# STM32L4xx-v1_2_0.net
KiCad netlist of a schematic drawn in EAGLE
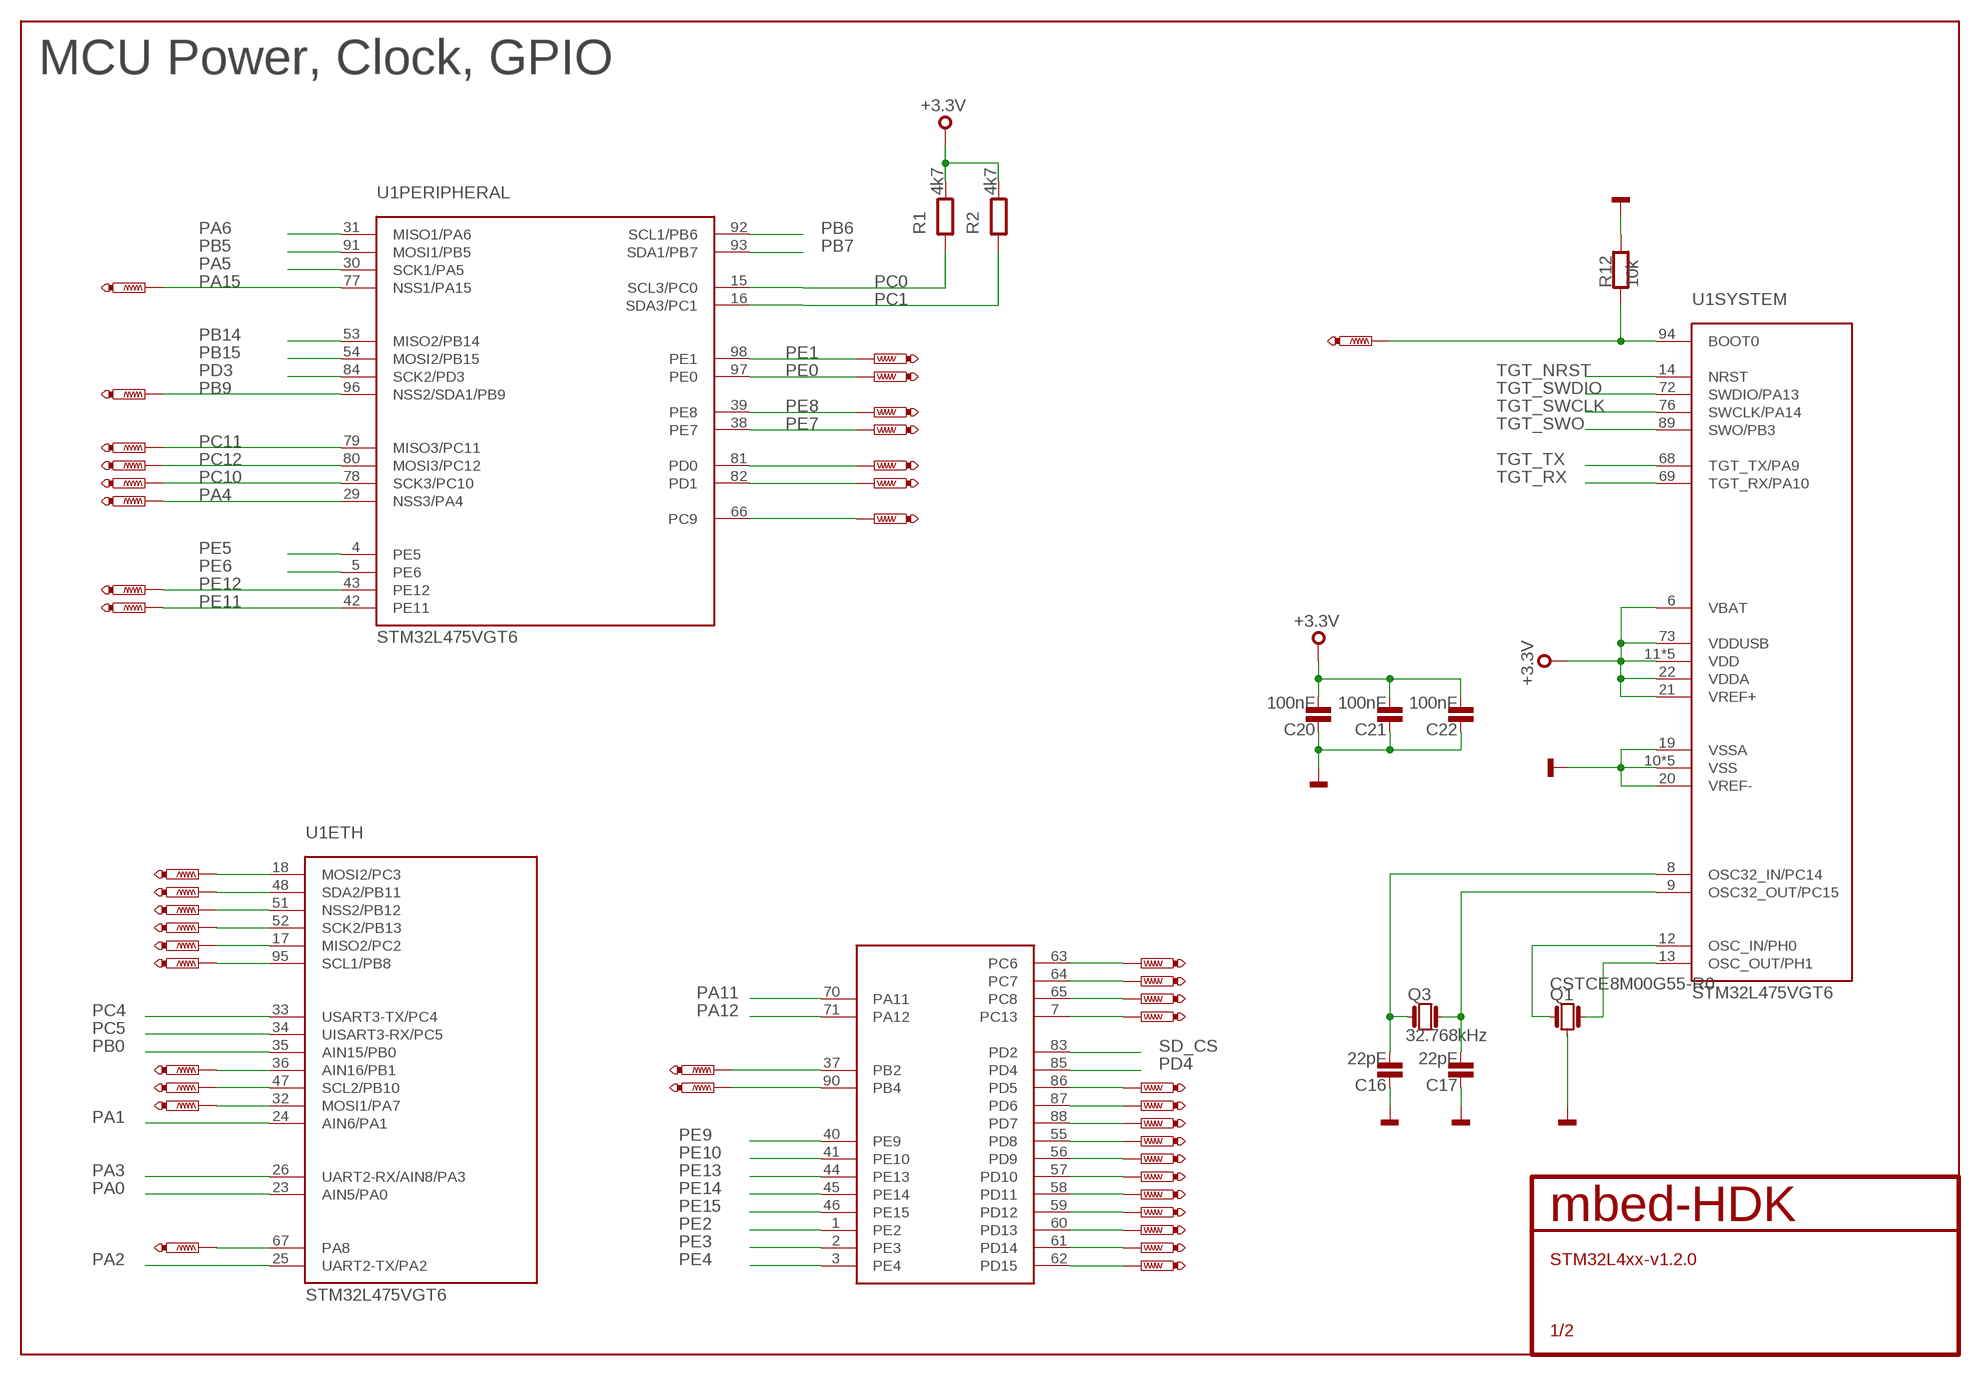
[diagram p0: schematic, sheet 1]
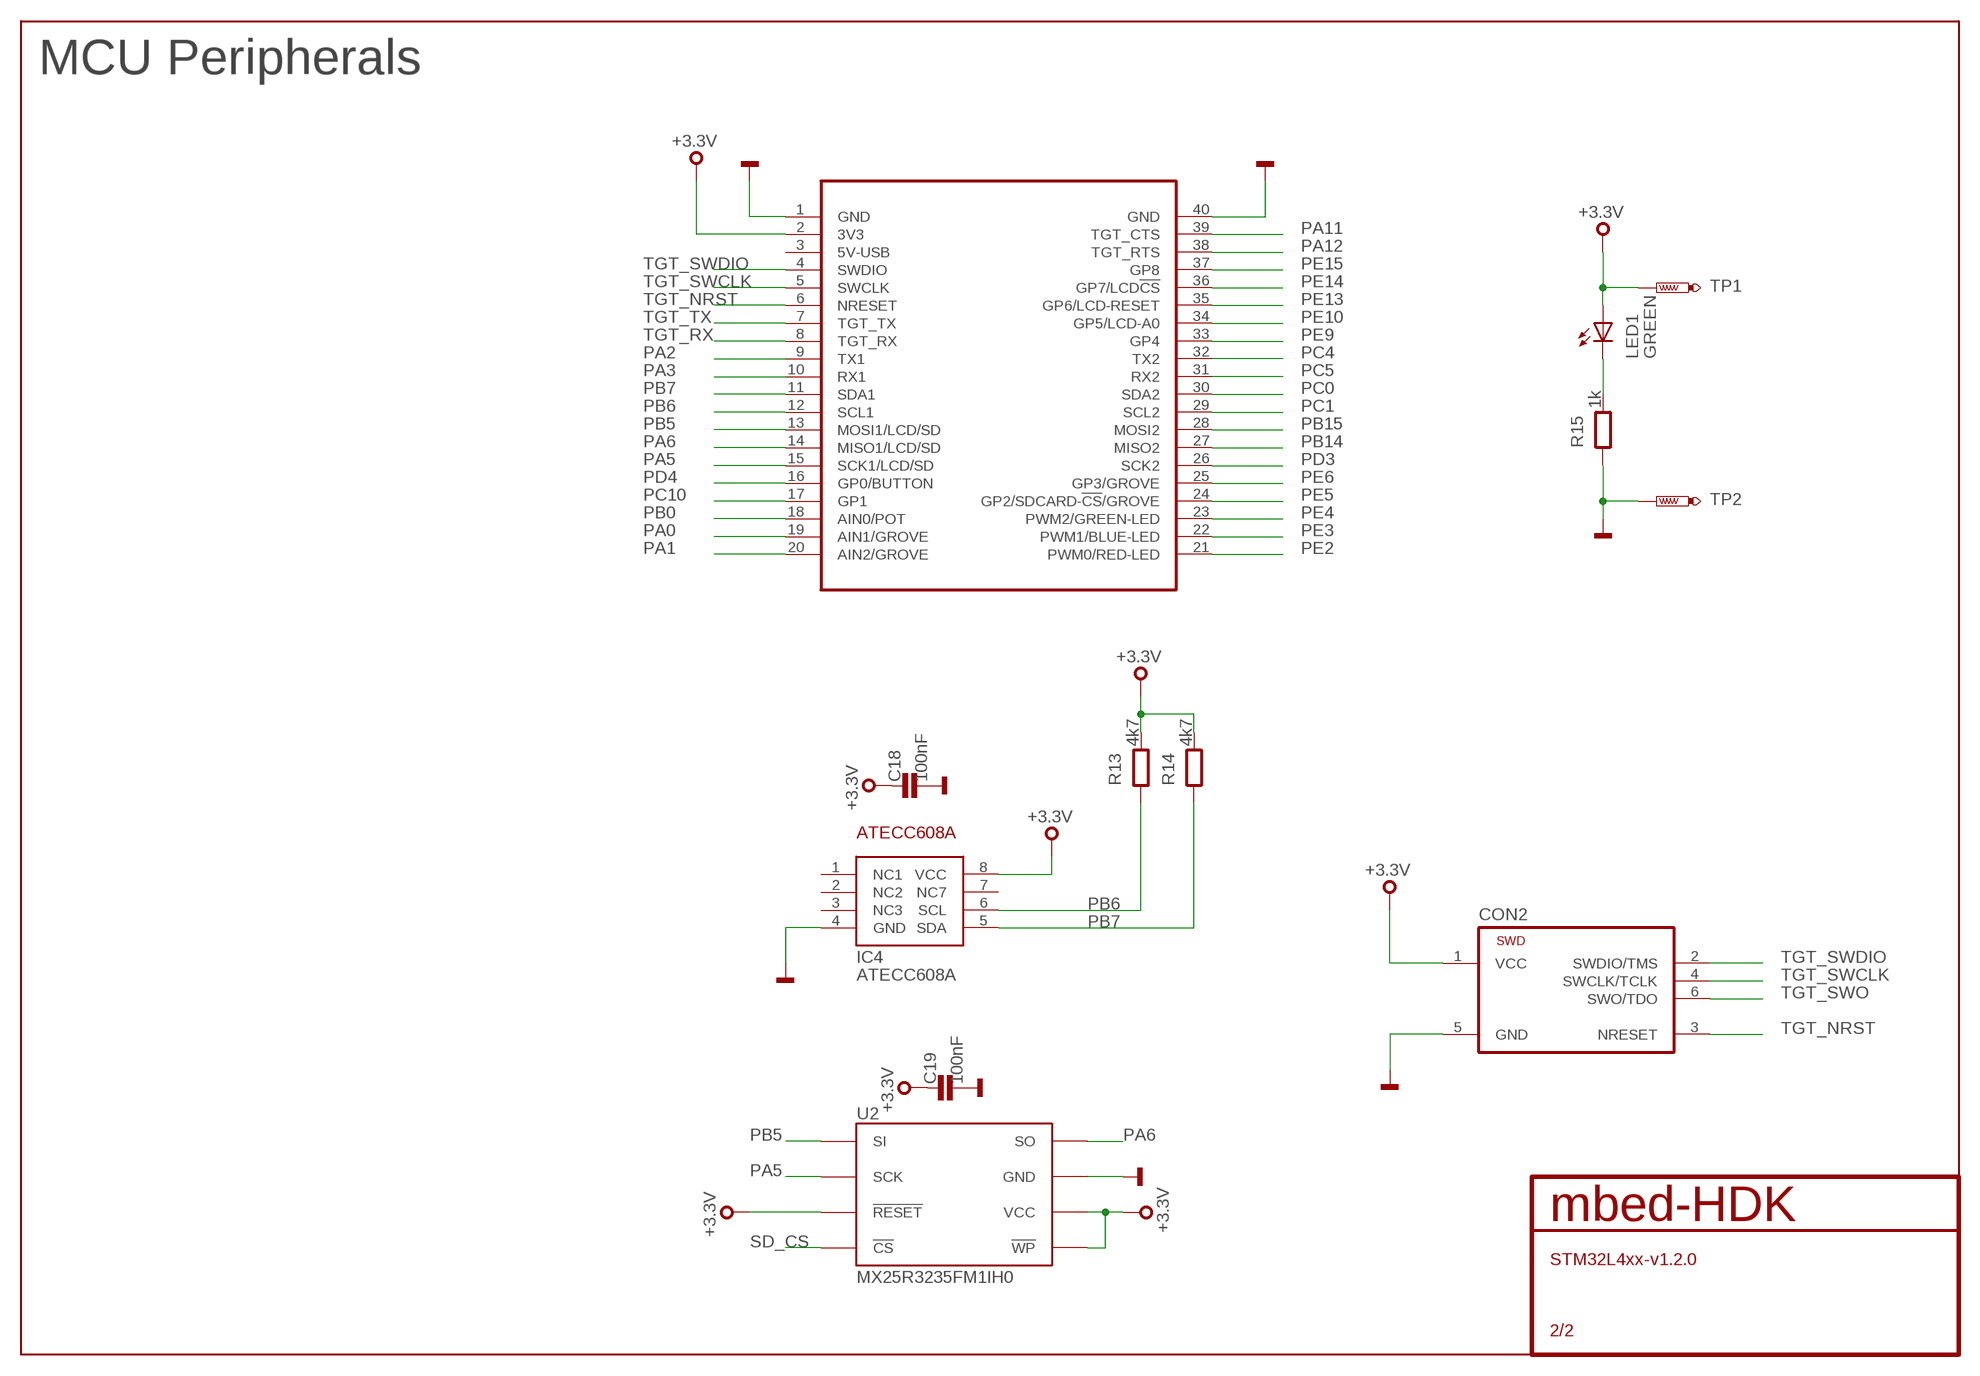
[diagram p1: schematic, sheet 2]

(export (version "E")
  (design (tool "Eeschema 10.0.6"))
  (components
    (comp (ref "C18")
      (value "100nF")
      (footprint "eagle-import:0402")
      (libsource (lib "eagle-import") (part "C0402"))
    )
    (comp (ref "C19")
      (value "100nF")
      (footprint "eagle-import:0402")
      (libsource (lib "eagle-import") (part "C0402"))
    )
    (comp (ref "CON2")
      (value "TC2030-CTX-NL")
      (footprint "eagle-import:TC2030-CTX-NL")
      (libsource (lib "eagle-import") (part "TC2030-CTX-NL"))
    )
    (comp (ref "IC4")
      (value "ATECC608A")
      (footprint "eagle-import:SO8")
      (libsource (lib "eagle-import") (part "ATECC608A"))
    )
    (comp (ref "LED1")
      (value "GREEN")
      (footprint "eagle-import:CHIPLED_0603")
      (fields (field (name "MF") "Wurth Electronics Inc"))
      (libsource (lib "eagle-import") (part "SMD_LED0603"))
    )
    (comp (ref "MOD1")
      (value "MODULE_DAUGHTER")
      (footprint "eagle-import:MODULE_DAUGHTER")
      (libsource (lib "eagle-import") (part "MODULE_DAUGHTER"))
    )
    (comp (ref "R13")
      (value "4k7")
      (footprint "eagle-import:0402")
      (libsource (lib "eagle-import") (part "R0402"))
    )
    (comp (ref "R14")
      (value "4k7")
      (footprint "eagle-import:0402")
      (libsource (lib "eagle-import") (part "R0402"))
    )
    (comp (ref "R15")
      (value "1k")
      (footprint "eagle-import:0603")
      (libsource (lib "eagle-import") (part "R0603"))
    )
    (comp (ref "TP1")
      (value "TEST_POINT-50R-PTH")
      (footprint "eagle-import:TP50-PTH")
      (libsource (lib "eagle-import") (part "TEST_POINT-50R-PTH"))
    )
    (comp (ref "TP2")
      (value "TEST_POINT-50R-PTH")
      (footprint "eagle-import:TP50-PTH")
      (libsource (lib "eagle-import") (part "TEST_POINT-50R-PTH"))
    )
    (comp (ref "U2")
      (value "MX25R3235FM1IH0")
      (footprint "eagle-import:SO8")
      (fields (field (name "MF") "Macronix"))
      (libsource (lib "eagle-import") (part "MX25R3235FM1IH0"))
    )
    (comp (ref "C16")
      (value "22pF")
      (footprint "eagle-import:0603")
      (libsource (lib "eagle-import") (part "C0603"))
    )
    (comp (ref "C17")
      (value "22pF")
      (footprint "eagle-import:0603")
      (libsource (lib "eagle-import") (part "C0603"))
    )
    (comp (ref "C20")
      (value "100nF")
      (footprint "eagle-import:0402")
      (libsource (lib "eagle-import") (part "C0402"))
    )
    (comp (ref "C21")
      (value "100nF")
      (footprint "eagle-import:0402")
      (libsource (lib "eagle-import") (part "C0402"))
    )
    (comp (ref "C22")
      (value "100nF")
      (footprint "eagle-import:0402")
      (libsource (lib "eagle-import") (part "C0402"))
    )
    (comp (ref "Q1")
      (value "CSTCE8M00G55-R0")
      (footprint "eagle-import:CSTCE8M00G55-R0")
      (fields (field (name "MF") "Murata"))
      (libsource (lib "eagle-import") (part "CSTCE8M00G55-R0"))
    )
    (comp (ref "Q3")
      (value "32.768kHz")
      (footprint "eagle-import:FC135")
      (libsource (lib "eagle-import") (part "GENERIC-CRYSTAL_FC135"))
    )
    (comp (ref "R1")
      (value "4k7")
      (footprint "eagle-import:0402")
      (libsource (lib "eagle-import") (part "R0402"))
    )
    (comp (ref "R2")
      (value "4k7")
      (footprint "eagle-import:0402")
      (libsource (lib "eagle-import") (part "R0402"))
    )
    (comp (ref "R12")
      (value "10k")
      (footprint "eagle-import:0402")
      (libsource (lib "eagle-import") (part "R0402"))
    )
    (comp (ref "TP3")
      (value "PTR1TP06R")
      (footprint "eagle-import:TP06R")
      (libsource (lib "eagle-import") (part "PTR1TP06R"))
    )
    (comp (ref "TP4")
      (value "PTR1TP06R")
      (footprint "eagle-import:TP06R")
      (libsource (lib "eagle-import") (part "PTR1TP06R"))
    )
    (comp (ref "TP5")
      (value "PTR1TP06R")
      (footprint "eagle-import:TP06R")
      (libsource (lib "eagle-import") (part "PTR1TP06R"))
    )
    (comp (ref "TP6")
      (value "PTR1TP06R")
      (footprint "eagle-import:TP06R")
      (libsource (lib "eagle-import") (part "PTR1TP06R"))
    )
    (comp (ref "TP7")
      (value "PTR1TP06R")
      (footprint "eagle-import:TP06R")
      (libsource (lib "eagle-import") (part "PTR1TP06R"))
    )
    (comp (ref "TP8")
      (value "PTR1TP06R")
      (footprint "eagle-import:TP06R")
      (libsource (lib "eagle-import") (part "PTR1TP06R"))
    )
    (comp (ref "TP9")
      (value "PTR1TP06R")
      (footprint "eagle-import:TP06R")
      (libsource (lib "eagle-import") (part "PTR1TP06R"))
    )
    (comp (ref "TP10")
      (value "PTR1TP06R")
      (footprint "eagle-import:TP06R")
      (libsource (lib "eagle-import") (part "PTR1TP06R"))
    )
    (comp (ref "TP11")
      (value "PTR1TP06R")
      (footprint "eagle-import:TP06R")
      (libsource (lib "eagle-import") (part "PTR1TP06R"))
    )
    (comp (ref "TP12")
      (value "PTR1TP06R")
      (footprint "eagle-import:TP06R")
      (libsource (lib "eagle-import") (part "PTR1TP06R"))
    )
    (comp (ref "TP13")
      (value "PTR1TP06R")
      (footprint "eagle-import:TP06R")
      (libsource (lib "eagle-import") (part "PTR1TP06R"))
    )
    (comp (ref "TP14")
      (value "PTR1TP06R")
      (footprint "eagle-import:TP06R")
      (libsource (lib "eagle-import") (part "PTR1TP06R"))
    )
    (comp (ref "TP15")
      (value "PTR1TP06R")
      (footprint "eagle-import:TP06R")
      (libsource (lib "eagle-import") (part "PTR1TP06R"))
    )
    (comp (ref "TP16")
      (value "PTR1TP06R")
      (footprint "eagle-import:TP06R")
      (libsource (lib "eagle-import") (part "PTR1TP06R"))
    )
    (comp (ref "TP17")
      (value "PTR1TP06R")
      (footprint "eagle-import:TP06R")
      (libsource (lib "eagle-import") (part "PTR1TP06R"))
    )
    (comp (ref "TP18")
      (value "PTR1TP06R")
      (footprint "eagle-import:TP06R")
      (libsource (lib "eagle-import") (part "PTR1TP06R"))
    )
    (comp (ref "TP19")
      (value "PTR1TP06R")
      (footprint "eagle-import:TP06R")
      (libsource (lib "eagle-import") (part "PTR1TP06R"))
    )
    (comp (ref "TP20")
      (value "PTR1TP06R")
      (footprint "eagle-import:TP06R")
      (libsource (lib "eagle-import") (part "PTR1TP06R"))
    )
    (comp (ref "TP21")
      (value "PTR1TP06R")
      (footprint "eagle-import:TP06R")
      (libsource (lib "eagle-import") (part "PTR1TP06R"))
    )
    (comp (ref "TP22")
      (value "PTR1TP06R")
      (footprint "eagle-import:TP06R")
      (libsource (lib "eagle-import") (part "PTR1TP06R"))
    )
    (comp (ref "TP23")
      (value "PTR1TP06R")
      (footprint "eagle-import:TP06R")
      (libsource (lib "eagle-import") (part "PTR1TP06R"))
    )
    (comp (ref "TP24")
      (value "PTR1TP06R")
      (footprint "eagle-import:TP06R")
      (libsource (lib "eagle-import") (part "PTR1TP06R"))
    )
    (comp (ref "TP25")
      (value "PTR1TP06R")
      (footprint "eagle-import:TP06R")
      (libsource (lib "eagle-import") (part "PTR1TP06R"))
    )
    (comp (ref "TP26")
      (value "PTR1TP06R")
      (footprint "eagle-import:TP06R")
      (libsource (lib "eagle-import") (part "PTR1TP06R"))
    )
    (comp (ref "TP27")
      (value "PTR1TP06R")
      (footprint "eagle-import:TP06R")
      (libsource (lib "eagle-import") (part "PTR1TP06R"))
    )
    (comp (ref "TP28")
      (value "PTR1TP06R")
      (footprint "eagle-import:TP06R")
      (libsource (lib "eagle-import") (part "PTR1TP06R"))
    )
    (comp (ref "TP29")
      (value "PTR1TP06R")
      (footprint "eagle-import:TP06R")
      (libsource (lib "eagle-import") (part "PTR1TP06R"))
    )
    (comp (ref "TP30")
      (value "PTR1TP06R")
      (footprint "eagle-import:TP06R")
      (libsource (lib "eagle-import") (part "PTR1TP06R"))
    )
    (comp (ref "TP31")
      (value "PTR1TP06R")
      (footprint "eagle-import:TP06R")
      (libsource (lib "eagle-import") (part "PTR1TP06R"))
    )
    (comp (ref "TP32")
      (value "PTR1TP06R")
      (footprint "eagle-import:TP06R")
      (libsource (lib "eagle-import") (part "PTR1TP06R"))
    )
    (comp (ref "TP33")
      (value "PTR1TP06R")
      (footprint "eagle-import:TP06R")
      (libsource (lib "eagle-import") (part "PTR1TP06R"))
    )
    (comp (ref "TP34")
      (value "PTR1TP06R")
      (footprint "eagle-import:TP06R")
      (libsource (lib "eagle-import") (part "PTR1TP06R"))
    )
    (comp (ref "TP35")
      (value "PTR1TP06R")
      (footprint "eagle-import:TP06R")
      (libsource (lib "eagle-import") (part "PTR1TP06R"))
    )
    (comp (ref "TP36")
      (value "PTR1TP06R")
      (footprint "eagle-import:TP06R")
      (libsource (lib "eagle-import") (part "PTR1TP06R"))
    )
    (comp (ref "TP37")
      (value "PTR1TP06R")
      (footprint "eagle-import:TP06R")
      (libsource (lib "eagle-import") (part "PTR1TP06R"))
    )
    (comp (ref "TP38")
      (value "PTR1TP06R")
      (footprint "eagle-import:TP06R")
      (libsource (lib "eagle-import") (part "PTR1TP06R"))
    )
    (comp (ref "TP39")
      (value "PTR1TP06R")
      (footprint "eagle-import:TP06R")
      (libsource (lib "eagle-import") (part "PTR1TP06R"))
    )
    (comp (ref "TP40")
      (value "PTR1TP06R")
      (footprint "eagle-import:TP06R")
      (libsource (lib "eagle-import") (part "PTR1TP06R"))
    )
    (comp (ref "TP41")
      (value "PTR1TP06R")
      (footprint "eagle-import:TP06R")
      (libsource (lib "eagle-import") (part "PTR1TP06R"))
    )
    (comp (ref "TP42")
      (value "PTR1TP06R")
      (footprint "eagle-import:TP06R")
      (libsource (lib "eagle-import") (part "PTR1TP06R"))
    )
    (comp (ref "TP43")
      (value "PTR1TP06R")
      (footprint "eagle-import:TP06R")
      (libsource (lib "eagle-import") (part "PTR1TP06R"))
    )
    (comp (ref "TP44")
      (value "PTR1TP06R")
      (footprint "eagle-import:TP06R")
      (libsource (lib "eagle-import") (part "PTR1TP06R"))
    )
    (comp (ref "TP45")
      (value "PTR1TP06R")
      (footprint "eagle-import:TP06R")
      (libsource (lib "eagle-import") (part "PTR1TP06R"))
    )
    (comp (ref "U1")
      (value "STM32L475VGT6")
      (footprint "eagle-import:QFP50P1600X1600X160-100N")
      (libsource (lib "eagle-import") (part "STM32L475VGT6"))
    )
  )
  (nets
    (net (code "1") (name "+3.3V") (class "Default")
      (node (ref "C18") (pin "1") (pinfunction "P$1_1") (pintype "passive"))
      (node (ref "C19") (pin "1") (pinfunction "P$1_1") (pintype "passive"))
      (node (ref "C20") (pin "2") (pinfunction "P$2_2") (pintype "passive"))
      (node (ref "C21") (pin "2") (pinfunction "P$2_2") (pintype "passive"))
      (node (ref "C22") (pin "2") (pinfunction "P$2_2") (pintype "passive"))
      (node (ref "CON2") (pin "1") (pinfunction "VCC_1") (pintype "passive"))
      (node (ref "IC4") (pin "8") (pinfunction "VCC_8") (pintype "bidirectional"))
      (node (ref "LED1") (pin "A") (pinfunction "A_A") (pintype "passive"))
      (node (ref "MOD1") (pin "2") (pinfunction "3V3_2") (pintype "bidirectional"))
      (node (ref "R1") (pin "2") (pinfunction "P$2_2") (pintype "passive"))
      (node (ref "R13") (pin "2") (pinfunction "P$2_2") (pintype "passive"))
      (node (ref "R14") (pin "2") (pinfunction "P$2_2") (pintype "passive"))
      (node (ref "R2") (pin "2") (pinfunction "P$2_2") (pintype "passive"))
      (node (ref "TP1") (pin "TP") (pinfunction "TP_TP") (pintype "input"))
      (node (ref "U1") (pin "100") (pinfunction "VDD_100") (pintype "power_in"))
      (node (ref "U1") (pin "11") (pinfunction "VDD_11") (pintype "power_in"))
      (node (ref "U1") (pin "21") (pinfunction "VREF+_21") (pintype "power_in"))
      (node (ref "U1") (pin "22") (pinfunction "VDDA_22") (pintype "power_in"))
      (node (ref "U1") (pin "28") (pinfunction "VDD_28") (pintype "power_in"))
      (node (ref "U1") (pin "50") (pinfunction "VDD_50") (pintype "power_in"))
      (node (ref "U1") (pin "6") (pinfunction "VBAT_6") (pintype "power_in"))
      (node (ref "U1") (pin "73") (pinfunction "VDDUSB_73") (pintype "power_in"))
      (node (ref "U1") (pin "75") (pinfunction "VDD_75") (pintype "power_in"))
      (node (ref "U2") (pin "3") (pinfunction "~{WP}_3") (pintype "bidirectional"))
      (node (ref "U2") (pin "7") (pinfunction "~{RESET}_7") (pintype "bidirectional"))
      (node (ref "U2") (pin "8") (pinfunction "VCC_8") (pintype "bidirectional"))
    )
    (net (code "2") (name "GND") (class "Default")
      (node (ref "C16") (pin "1") (pinfunction "P$1_1") (pintype "passive"))
      (node (ref "C17") (pin "1") (pinfunction "P$1_1") (pintype "passive"))
      (node (ref "C18") (pin "2") (pinfunction "P$2_2") (pintype "passive"))
      (node (ref "C19") (pin "2") (pinfunction "P$2_2") (pintype "passive"))
      (node (ref "C20") (pin "1") (pinfunction "P$1_1") (pintype "passive"))
      (node (ref "C21") (pin "1") (pinfunction "P$1_1") (pintype "passive"))
      (node (ref "C22") (pin "1") (pinfunction "P$1_1") (pintype "passive"))
      (node (ref "CON2") (pin "5") (pinfunction "GND_5") (pintype "passive"))
      (node (ref "IC4") (pin "4") (pinfunction "GND_4") (pintype "bidirectional"))
      (node (ref "MOD1") (pin "1") (pinfunction "GND_1") (pintype "bidirectional"))
      (node (ref "MOD1") (pin "40") (pinfunction "GND_40") (pintype "bidirectional"))
      (node (ref "Q1") (pin "2") (pinfunction "2_2") (pintype "passive"))
      (node (ref "R12") (pin "2") (pinfunction "P$2_2") (pintype "passive"))
      (node (ref "R15") (pin "1") (pinfunction "P$1_1") (pintype "passive"))
      (node (ref "TP2") (pin "TP") (pinfunction "TP_TP") (pintype "input"))
      (node (ref "U1") (pin "10") (pinfunction "VSS_10") (pintype "power_in"))
      (node (ref "U1") (pin "19") (pinfunction "VSSA_19") (pintype "power_in"))
      (node (ref "U1") (pin "20") (pinfunction "VREF-_20") (pintype "power_in"))
      (node (ref "U1") (pin "27") (pinfunction "VSS_27") (pintype "power_in"))
      (node (ref "U1") (pin "49") (pinfunction "VSS_49") (pintype "power_in"))
      (node (ref "U1") (pin "74") (pinfunction "VSS_74") (pintype "power_in"))
      (node (ref "U1") (pin "99") (pinfunction "VSS_99") (pintype "power_in"))
      (node (ref "U2") (pin "4") (pinfunction "GND_4") (pintype "bidirectional"))
    )
    (net (code "3") (name "Net-(C16-P$2)") (class "Default")
      (node (ref "C16") (pin "2") (pinfunction "P$2_2") (pintype "passive"))
      (node (ref "Q3") (pin "X1") (pinfunction "1_X1") (pintype "passive"))
      (node (ref "U1") (pin "8") (pinfunction "OSC32_IN/PC14_8") (pintype "bidirectional"))
    )
    (net (code "4") (name "Net-(C17-P$2)") (class "Default")
      (node (ref "C17") (pin "2") (pinfunction "P$2_2") (pintype "passive"))
      (node (ref "Q3") (pin "X2") (pinfunction "2_X2") (pintype "passive"))
      (node (ref "U1") (pin "9") (pinfunction "OSC32_OUT/PC15_9") (pintype "bidirectional"))
    )
    (net (code "5") (name "Net-(R12-P$1)") (class "Default")
      (node (ref "R12") (pin "1") (pinfunction "P$1_1") (pintype "passive"))
      (node (ref "TP6") (pin "TP") (pinfunction "TP_TP") (pintype "input"))
      (node (ref "U1") (pin "94") (pinfunction "BOOT0_94") (pintype "input"))
    )
    (net (code "6") (name "Net-(R15-P$2)") (class "Default")
      (node (ref "LED1") (pin "C") (pinfunction "C_C") (pintype "passive"))
      (node (ref "R15") (pin "2") (pinfunction "P$2_2") (pintype "passive"))
    )
    (net (code "7") (name "Net-(U1A-AIN16{slash}PB1)") (class "Default")
      (node (ref "TP34") (pin "TP") (pinfunction "TP_TP") (pintype "input"))
      (node (ref "U1") (pin "36") (pinfunction "AIN16/PB1_36") (pintype "bidirectional"))
    )
    (net (code "8") (name "Net-(U1A-MISO2{slash}PC2)") (class "Default")
      (node (ref "TP31") (pin "TP") (pinfunction "TP_TP") (pintype "input"))
      (node (ref "U1") (pin "17") (pinfunction "MISO2/PC2_17") (pintype "bidirectional"))
    )
    (net (code "9") (name "Net-(U1A-MOSI1{slash}PA7)") (class "Default")
      (node (ref "TP35") (pin "TP") (pinfunction "TP_TP") (pintype "input"))
      (node (ref "U1") (pin "32") (pinfunction "MOSI1/PA7_32") (pintype "bidirectional"))
    )
    (net (code "10") (name "Net-(U1A-MOSI2{slash}PC3)") (class "Default")
      (node (ref "TP27") (pin "TP") (pinfunction "TP_TP") (pintype "input"))
      (node (ref "U1") (pin "18") (pinfunction "MOSI2/PC3_18") (pintype "bidirectional"))
    )
    (net (code "11") (name "Net-(U1A-NSS2{slash}PB12)") (class "Default")
      (node (ref "TP29") (pin "TP") (pinfunction "TP_TP") (pintype "input"))
      (node (ref "U1") (pin "51") (pinfunction "NSS2/PB12_51") (pintype "bidirectional"))
    )
    (net (code "12") (name "Net-(U1A-PA8)") (class "Default")
      (node (ref "TP33") (pin "TP") (pinfunction "TP_TP") (pintype "input"))
      (node (ref "U1") (pin "67") (pinfunction "PA8_67") (pintype "bidirectional"))
    )
    (net (code "13") (name "Net-(U1A-SCK2{slash}PB13)") (class "Default")
      (node (ref "TP30") (pin "TP") (pinfunction "TP_TP") (pintype "input"))
      (node (ref "U1") (pin "52") (pinfunction "SCK2/PB13_52") (pintype "bidirectional"))
    )
    (net (code "14") (name "Net-(U1A-SCL1{slash}PB8)") (class "Default")
      (node (ref "TP32") (pin "TP") (pinfunction "TP_TP") (pintype "input"))
      (node (ref "U1") (pin "95") (pinfunction "SCL1/PB8_95") (pintype "bidirectional"))
    )
    (net (code "15") (name "Net-(U1A-SCL2{slash}PB10)") (class "Default")
      (node (ref "TP36") (pin "TP") (pinfunction "TP_TP") (pintype "input"))
      (node (ref "U1") (pin "47") (pinfunction "SCL2/PB10_47") (pintype "bidirectional"))
    )
    (net (code "16") (name "Net-(U1A-SDA2{slash}PB11)") (class "Default")
      (node (ref "TP28") (pin "TP") (pinfunction "TP_TP") (pintype "input"))
      (node (ref "U1") (pin "48") (pinfunction "SDA2/PB11_48") (pintype "bidirectional"))
    )
    (net (code "17") (name "Net-(U1B-PB2)") (class "Default")
      (node (ref "TP26") (pin "TP") (pinfunction "TP_TP") (pintype "input"))
      (node (ref "U1") (pin "37") (pinfunction "PB2_37") (pintype "bidirectional"))
    )
    (net (code "18") (name "Net-(U1B-PB4)") (class "Default")
      (node (ref "TP11") (pin "TP") (pinfunction "TP_TP") (pintype "input"))
      (node (ref "U1") (pin "90") (pinfunction "PB4_90") (pintype "bidirectional"))
    )
    (net (code "19") (name "Net-(U1B-PC6)") (class "Default")
      (node (ref "TP15") (pin "TP") (pinfunction "TP_TP") (pintype "input"))
      (node (ref "U1") (pin "63") (pinfunction "PC6_63") (pintype "bidirectional"))
    )
    (net (code "20") (name "Net-(U1B-PC7)") (class "Default")
      (node (ref "TP16") (pin "TP") (pinfunction "TP_TP") (pintype "input"))
      (node (ref "U1") (pin "64") (pinfunction "PC7_64") (pintype "bidirectional"))
    )
    (net (code "21") (name "Net-(U1B-PC8)") (class "Default")
      (node (ref "TP17") (pin "TP") (pinfunction "TP_TP") (pintype "input"))
      (node (ref "U1") (pin "65") (pinfunction "PC8_65") (pintype "bidirectional"))
    )
    (net (code "22") (name "Net-(U1B-PC13)") (class "Default")
      (node (ref "TP25") (pin "TP") (pinfunction "TP_TP") (pintype "input"))
      (node (ref "U1") (pin "7") (pinfunction "PC13_7") (pintype "bidirectional"))
    )
    (net (code "23") (name "Net-(U1B-PD5)") (class "Default")
      (node (ref "TP20") (pin "TP") (pinfunction "TP_TP") (pintype "input"))
      (node (ref "U1") (pin "86") (pinfunction "PD5_86") (pintype "bidirectional"))
    )
    (net (code "24") (name "Net-(U1B-PD6)") (class "Default")
      (node (ref "TP19") (pin "TP") (pinfunction "TP_TP") (pintype "input"))
      (node (ref "U1") (pin "87") (pinfunction "PD6_87") (pintype "bidirectional"))
    )
    (net (code "25") (name "Net-(U1B-PD7)") (class "Default")
      (node (ref "TP18") (pin "TP") (pinfunction "TP_TP") (pintype "input"))
      (node (ref "U1") (pin "88") (pinfunction "PD7_88") (pintype "bidirectional"))
    )
    (net (code "26") (name "Net-(U1B-PD8)") (class "Default")
      (node (ref "TP5") (pin "TP") (pinfunction "TP_TP") (pintype "input"))
      (node (ref "U1") (pin "55") (pinfunction "PD8_55") (pintype "bidirectional"))
    )
    (net (code "27") (name "Net-(U1B-PD9)") (class "Default")
      (node (ref "TP13") (pin "TP") (pinfunction "TP_TP") (pintype "input"))
      (node (ref "U1") (pin "56") (pinfunction "PD9_56") (pintype "bidirectional"))
    )
    (net (code "28") (name "Net-(U1B-PD10)") (class "Default")
      (node (ref "TP10") (pin "TP") (pinfunction "TP_TP") (pintype "input"))
      (node (ref "U1") (pin "57") (pinfunction "PD10_57") (pintype "bidirectional"))
    )
    (net (code "29") (name "Net-(U1B-PD11)") (class "Default")
      (node (ref "TP22") (pin "TP") (pinfunction "TP_TP") (pintype "input"))
      (node (ref "U1") (pin "58") (pinfunction "PD11_58") (pintype "bidirectional"))
    )
    (net (code "30") (name "Net-(U1B-PD12)") (class "Default")
      (node (ref "TP23") (pin "TP") (pinfunction "TP_TP") (pintype "input"))
      (node (ref "U1") (pin "59") (pinfunction "PD12_59") (pintype "bidirectional"))
    )
    (net (code "31") (name "Net-(U1B-PD13)") (class "Default")
      (node (ref "TP12") (pin "TP") (pinfunction "TP_TP") (pintype "input"))
      (node (ref "U1") (pin "60") (pinfunction "PD13_60") (pintype "bidirectional"))
    )
    (net (code "32") (name "Net-(U1B-PD14)") (class "Default")
      (node (ref "TP24") (pin "TP") (pinfunction "TP_TP") (pintype "input"))
      (node (ref "U1") (pin "61") (pinfunction "PD14_61") (pintype "bidirectional"))
    )
    (net (code "33") (name "Net-(U1B-PD15)") (class "Default")
      (node (ref "TP21") (pin "TP") (pinfunction "TP_TP") (pintype "input"))
      (node (ref "U1") (pin "62") (pinfunction "PD15_62") (pintype "bidirectional"))
    )
    (net (code "34") (name "Net-(U1C-PC9)") (class "Default")
      (node (ref "TP7") (pin "TP") (pinfunction "TP_TP") (pintype "input"))
      (node (ref "U1") (pin "66") (pinfunction "PC9_66") (pintype "bidirectional"))
    )
    (net (code "35") (name "Net-(U1C-PD0)") (class "Default")
      (node (ref "TP3") (pin "TP") (pinfunction "TP_TP") (pintype "input"))
      (node (ref "U1") (pin "81") (pinfunction "PD0_81") (pintype "bidirectional"))
    )
    (net (code "36") (name "Net-(U1C-PD1)") (class "Default")
      (node (ref "TP4") (pin "TP") (pinfunction "TP_TP") (pintype "input"))
      (node (ref "U1") (pin "82") (pinfunction "PD1_82") (pintype "bidirectional"))
    )
    (net (code "37") (name "Net-(U1D-OSC_IN{slash}PH0)") (class "Default")
      (node (ref "Q1") (pin "1") (pinfunction "1_1") (pintype "passive"))
      (node (ref "U1") (pin "12") (pinfunction "OSC_IN/PH0_12") (pintype "bidirectional"))
    )
    (net (code "38") (name "Net-(U1D-OSC_OUT{slash}PH1)") (class "Default")
      (node (ref "Q1") (pin "3") (pinfunction "3_3") (pintype "passive"))
      (node (ref "U1") (pin "13") (pinfunction "OSC_OUT/PH1_13") (pintype "bidirectional"))
    )
    (net (code "39") (name "PA0") (class "Default")
      (node (ref "MOD1") (pin "19") (pinfunction "AIN1/GROVE_19") (pintype "bidirectional"))
      (node (ref "U1") (pin "23") (pinfunction "AIN5/PA0_23") (pintype "bidirectional"))
    )
    (net (code "40") (name "PA1") (class "Default")
      (node (ref "MOD1") (pin "20") (pinfunction "AIN2/GROVE_20") (pintype "bidirectional"))
      (node (ref "U1") (pin "24") (pinfunction "AIN6/PA1_24") (pintype "bidirectional"))
    )
    (net (code "41") (name "PA2") (class "Default")
      (node (ref "MOD1") (pin "9") (pinfunction "TX1_9") (pintype "bidirectional"))
      (node (ref "U1") (pin "25") (pinfunction "UART2-TX/PA2_25") (pintype "bidirectional"))
    )
    (net (code "42") (name "PA3") (class "Default")
      (node (ref "MOD1") (pin "10") (pinfunction "RX1_10") (pintype "bidirectional"))
      (node (ref "U1") (pin "26") (pinfunction "UART2-RX/AIN8/PA3_26") (pintype "bidirectional"))
    )
    (net (code "43") (name "PA4") (class "Default")
      (node (ref "TP44") (pin "TP") (pinfunction "TP_TP") (pintype "input"))
      (node (ref "U1") (pin "29") (pinfunction "NSS3/PA4_29") (pintype "bidirectional"))
    )
    (net (code "44") (name "PA5") (class "Default")
      (node (ref "MOD1") (pin "15") (pinfunction "SCK1/LCD/SD_15") (pintype "bidirectional"))
      (node (ref "U1") (pin "30") (pinfunction "SCK1/PA5_30") (pintype "bidirectional"))
      (node (ref "U2") (pin "6") (pinfunction "SCK_6") (pintype "bidirectional"))
    )
    (net (code "45") (name "PA6") (class "Default")
      (node (ref "MOD1") (pin "14") (pinfunction "MISO1/LCD/SD_14") (pintype "bidirectional"))
      (node (ref "U1") (pin "31") (pinfunction "MISO1/PA6_31") (pintype "bidirectional"))
      (node (ref "U2") (pin "2") (pinfunction "SO_2") (pintype "bidirectional"))
    )
    (net (code "46") (name "PA11") (class "Default")
      (node (ref "MOD1") (pin "39") (pinfunction "TGT_CTS_39") (pintype "bidirectional"))
      (node (ref "U1") (pin "70") (pinfunction "PA11_70") (pintype "bidirectional"))
    )
    (net (code "47") (name "PA12") (class "Default")
      (node (ref "MOD1") (pin "38") (pinfunction "TGT_RTS_38") (pintype "bidirectional"))
      (node (ref "U1") (pin "71") (pinfunction "PA12_71") (pintype "bidirectional"))
    )
    (net (code "48") (name "PA15") (class "Default")
      (node (ref "TP37") (pin "TP") (pinfunction "TP_TP") (pintype "input"))
      (node (ref "U1") (pin "77") (pinfunction "NSS1/PA15_77") (pintype "bidirectional"))
    )
    (net (code "49") (name "PB0") (class "Default")
      (node (ref "MOD1") (pin "18") (pinfunction "AIN0/POT_18") (pintype "bidirectional"))
      (node (ref "U1") (pin "35") (pinfunction "AIN15/PB0_35") (pintype "bidirectional"))
    )
    (net (code "50") (name "PB5") (class "Default")
      (node (ref "MOD1") (pin "13") (pinfunction "MOSI1/LCD/SD_13") (pintype "bidirectional"))
      (node (ref "U1") (pin "91") (pinfunction "MOSI1/PB5_91") (pintype "bidirectional"))
      (node (ref "U2") (pin "5") (pinfunction "SI_5") (pintype "bidirectional"))
    )
    (net (code "51") (name "PB6") (class "Default")
      (node (ref "IC4") (pin "6") (pinfunction "SCL_6") (pintype "bidirectional"))
      (node (ref "MOD1") (pin "12") (pinfunction "SCL1_12") (pintype "bidirectional"))
      (node (ref "R13") (pin "1") (pinfunction "P$1_1") (pintype "passive"))
      (node (ref "U1") (pin "92") (pinfunction "SCL1/PB6_92") (pintype "bidirectional"))
    )
    (net (code "52") (name "PB7") (class "Default")
      (node (ref "IC4") (pin "5") (pinfunction "SDA_5") (pintype "bidirectional"))
      (node (ref "MOD1") (pin "11") (pinfunction "SDA1_11") (pintype "bidirectional"))
      (node (ref "R14") (pin "1") (pinfunction "P$1_1") (pintype "passive"))
      (node (ref "U1") (pin "93") (pinfunction "SDA1/PB7_93") (pintype "bidirectional"))
    )
    (net (code "53") (name "PB9") (class "Default")
      (node (ref "TP14") (pin "TP") (pinfunction "TP_TP") (pintype "input"))
      (node (ref "U1") (pin "96") (pinfunction "NSS2/SDA1/PB9_96") (pintype "bidirectional"))
    )
    (net (code "54") (name "PB14") (class "Default")
      (node (ref "MOD1") (pin "27") (pinfunction "MISO2_27") (pintype "bidirectional"))
      (node (ref "U1") (pin "53") (pinfunction "MISO2/PB14_53") (pintype "bidirectional"))
    )
    (net (code "55") (name "PB15") (class "Default")
      (node (ref "MOD1") (pin "28") (pinfunction "MOSI2_28") (pintype "bidirectional"))
      (node (ref "U1") (pin "54") (pinfunction "MOSI2/PB15_54") (pintype "bidirectional"))
    )
    (net (code "56") (name "PC0") (class "Default")
      (node (ref "MOD1") (pin "30") (pinfunction "SDA2_30") (pintype "bidirectional"))
      (node (ref "R1") (pin "1") (pinfunction "P$1_1") (pintype "passive"))
      (node (ref "U1") (pin "15") (pinfunction "SCL3/PC0_15") (pintype "bidirectional"))
    )
    (net (code "57") (name "PC1") (class "Default")
      (node (ref "MOD1") (pin "29") (pinfunction "SCL2_29") (pintype "bidirectional"))
      (node (ref "R2") (pin "1") (pinfunction "P$1_1") (pintype "passive"))
      (node (ref "U1") (pin "16") (pinfunction "SDA3/PC1_16") (pintype "bidirectional"))
    )
    (net (code "58") (name "PC4") (class "Default")
      (node (ref "MOD1") (pin "32") (pinfunction "TX2_32") (pintype "bidirectional"))
      (node (ref "U1") (pin "33") (pinfunction "USART3-TX/PC4_33") (pintype "bidirectional"))
    )
    (net (code "59") (name "PC5") (class "Default")
      (node (ref "MOD1") (pin "31") (pinfunction "RX2_31") (pintype "bidirectional"))
      (node (ref "U1") (pin "34") (pinfunction "UISART3-RX/PC5_34") (pintype "bidirectional"))
    )
    (net (code "60") (name "PC10") (class "Default")
      (node (ref "MOD1") (pin "17") (pinfunction "GP1_17") (pintype "bidirectional"))
      (node (ref "TP43") (pin "TP") (pinfunction "TP_TP") (pintype "input"))
      (node (ref "U1") (pin "78") (pinfunction "SCK3/PC10_78") (pintype "bidirectional"))
    )
    (net (code "61") (name "PC11") (class "Default")
      (node (ref "TP41") (pin "TP") (pinfunction "TP_TP") (pintype "input"))
      (node (ref "U1") (pin "79") (pinfunction "MISO3/PC11_79") (pintype "bidirectional"))
    )
    (net (code "62") (name "PC12") (class "Default")
      (node (ref "TP42") (pin "TP") (pinfunction "TP_TP") (pintype "input"))
      (node (ref "U1") (pin "80") (pinfunction "MOSI3/PC12_80") (pintype "bidirectional"))
    )
    (net (code "63") (name "PD3") (class "Default")
      (node (ref "MOD1") (pin "26") (pinfunction "SCK2_26") (pintype "bidirectional"))
      (node (ref "U1") (pin "84") (pinfunction "SCK2/PD3_84") (pintype "bidirectional"))
    )
    (net (code "64") (name "PD4") (class "Default")
      (node (ref "MOD1") (pin "16") (pinfunction "GP0/BUTTON_16") (pintype "bidirectional"))
      (node (ref "U1") (pin "85") (pinfunction "PD4_85") (pintype "bidirectional"))
    )
    (net (code "65") (name "PE0") (class "Default")
      (node (ref "TP39") (pin "TP") (pinfunction "TP_TP") (pintype "input"))
      (node (ref "U1") (pin "97") (pinfunction "PE0_97") (pintype "bidirectional"))
    )
    (net (code "66") (name "PE1") (class "Default")
      (node (ref "TP38") (pin "TP") (pinfunction "TP_TP") (pintype "input"))
      (node (ref "U1") (pin "98") (pinfunction "PE1_98") (pintype "bidirectional"))
    )
    (net (code "67") (name "PE2") (class "Default")
      (node (ref "MOD1") (pin "21") (pinfunction "PWM0/RED-LED_21") (pintype "bidirectional"))
      (node (ref "U1") (pin "1") (pinfunction "PE2_1") (pintype "bidirectional"))
    )
    (net (code "68") (name "PE3") (class "Default")
      (node (ref "MOD1") (pin "22") (pinfunction "PWM1/BLUE-LED_22") (pintype "bidirectional"))
      (node (ref "U1") (pin "2") (pinfunction "PE3_2") (pintype "bidirectional"))
    )
    (net (code "69") (name "PE4") (class "Default")
      (node (ref "MOD1") (pin "23") (pinfunction "PWM2/GREEN-LED_23") (pintype "bidirectional"))
      (node (ref "U1") (pin "3") (pinfunction "PE4_3") (pintype "bidirectional"))
    )
    (net (code "70") (name "PE5") (class "Default")
      (node (ref "MOD1") (pin "24") (pinfunction "GP2/SDCARD-~{CS}/GROVE_24") (pintype "bidirectional"))
      (node (ref "U1") (pin "4") (pinfunction "PE5_4") (pintype "bidirectional"))
    )
    (net (code "71") (name "PE6") (class "Default")
      (node (ref "MOD1") (pin "25") (pinfunction "GP3/GROVE_25") (pintype "bidirectional"))
      (node (ref "U1") (pin "5") (pinfunction "PE6_5") (pintype "bidirectional"))
    )
    (net (code "72") (name "PE7") (class "Default")
      (node (ref "TP45") (pin "TP") (pinfunction "TP_TP") (pintype "input"))
      (node (ref "U1") (pin "38") (pinfunction "PE7_38") (pintype "bidirectional"))
    )
    (net (code "73") (name "PE8") (class "Default")
      (node (ref "TP40") (pin "TP") (pinfunction "TP_TP") (pintype "input"))
      (node (ref "U1") (pin "39") (pinfunction "PE8_39") (pintype "bidirectional"))
    )
    (net (code "74") (name "PE9") (class "Default")
      (node (ref "MOD1") (pin "33") (pinfunction "GP4_33") (pintype "bidirectional"))
      (node (ref "U1") (pin "40") (pinfunction "PE9_40") (pintype "bidirectional"))
    )
    (net (code "75") (name "PE10") (class "Default")
      (node (ref "MOD1") (pin "34") (pinfunction "GP5/LCD-A0_34") (pintype "bidirectional"))
      (node (ref "U1") (pin "41") (pinfunction "PE10_41") (pintype "bidirectional"))
    )
    (net (code "76") (name "PE11") (class "Default")
      (node (ref "TP8") (pin "TP") (pinfunction "TP_TP") (pintype "input"))
      (node (ref "U1") (pin "42") (pinfunction "PE11_42") (pintype "bidirectional"))
    )
    (net (code "77") (name "PE12") (class "Default")
      (node (ref "TP9") (pin "TP") (pinfunction "TP_TP") (pintype "input"))
      (node (ref "U1") (pin "43") (pinfunction "PE12_43") (pintype "bidirectional"))
    )
    (net (code "78") (name "PE13") (class "Default")
      (node (ref "MOD1") (pin "35") (pinfunction "GP6/LCD-RESET_35") (pintype "bidirectional"))
      (node (ref "U1") (pin "44") (pinfunction "PE13_44") (pintype "bidirectional"))
    )
    (net (code "79") (name "PE14") (class "Default")
      (node (ref "MOD1") (pin "36") (pinfunction "GP7/LCD~{CS}_36") (pintype "bidirectional"))
      (node (ref "U1") (pin "45") (pinfunction "PE14_45") (pintype "bidirectional"))
    )
    (net (code "80") (name "PE15") (class "Default")
      (node (ref "MOD1") (pin "37") (pinfunction "GP8_37") (pintype "bidirectional"))
      (node (ref "U1") (pin "46") (pinfunction "PE15_46") (pintype "bidirectional"))
    )
    (net (code "81") (name "SD_CS") (class "Default")
      (node (ref "U1") (pin "83") (pinfunction "PD2_83") (pintype "bidirectional"))
      (node (ref "U2") (pin "1") (pinfunction "~{CS}_1") (pintype "bidirectional"))
    )
    (net (code "82") (name "TGT_NRST") (class "Default")
      (node (ref "CON2") (pin "3") (pinfunction "NRESET_3") (pintype "passive"))
      (node (ref "MOD1") (pin "6") (pinfunction "NRESET_6") (pintype "bidirectional"))
      (node (ref "U1") (pin "14") (pinfunction "NRST_14") (pintype "bidirectional"))
    )
    (net (code "83") (name "TGT_RX") (class "Default")
      (node (ref "MOD1") (pin "8") (pinfunction "TGT_RX_8") (pintype "bidirectional"))
      (node (ref "U1") (pin "69") (pinfunction "TGT_RX/PA10_69") (pintype "bidirectional"))
    )
    (net (code "84") (name "TGT_SWCLK") (class "Default")
      (node (ref "CON2") (pin "4") (pinfunction "SWCLK/TCLK_4") (pintype "passive"))
      (node (ref "MOD1") (pin "5") (pinfunction "SWCLK_5") (pintype "bidirectional"))
      (node (ref "U1") (pin "76") (pinfunction "SWCLK/PA14_76") (pintype "bidirectional"))
    )
    (net (code "85") (name "TGT_SWDIO") (class "Default")
      (node (ref "CON2") (pin "2") (pinfunction "SWDIO/TMS_2") (pintype "passive"))
      (node (ref "MOD1") (pin "4") (pinfunction "SWDIO_4") (pintype "bidirectional"))
      (node (ref "U1") (pin "72") (pinfunction "SWDIO/PA13_72") (pintype "bidirectional"))
    )
    (net (code "86") (name "TGT_SWO") (class "Default")
      (node (ref "CON2") (pin "6") (pinfunction "SWO/TDO_6") (pintype "passive"))
      (node (ref "U1") (pin "89") (pinfunction "SWO/PB3_89") (pintype "bidirectional"))
    )
    (net (code "87") (name "TGT_TX") (class "Default")
      (node (ref "MOD1") (pin "7") (pinfunction "TGT_TX_7") (pintype "bidirectional"))
      (node (ref "U1") (pin "68") (pinfunction "TGT_TX/PA9_68") (pintype "bidirectional"))
    )
    (net (code "88") (name "unconnected-(IC4-NC1-Pad1)") (class "Default")
      (node (ref "IC4") (pin "1") (pinfunction "NC1_1") (pintype "bidirectional"))
    )
    (net (code "89") (name "unconnected-(IC4-NC2-Pad2)") (class "Default")
      (node (ref "IC4") (pin "2") (pinfunction "NC2_2") (pintype "bidirectional"))
    )
    (net (code "90") (name "unconnected-(IC4-NC3-Pad3)") (class "Default")
      (node (ref "IC4") (pin "3") (pinfunction "NC3_3") (pintype "bidirectional"))
    )
    (net (code "91") (name "unconnected-(IC4-NC7-Pad7)") (class "Default")
      (node (ref "IC4") (pin "7") (pinfunction "NC7_7") (pintype "bidirectional"))
    )
    (net (code "92") (name "unconnected-(MOD1-5V-USB-Pad3)") (class "Default")
      (node (ref "MOD1") (pin "3") (pinfunction "5V-USB_3") (pintype "bidirectional"))
    )
  )
)
